# LM709_schematic.net
KiCad netlist of a schematic drawn in Altium Designer
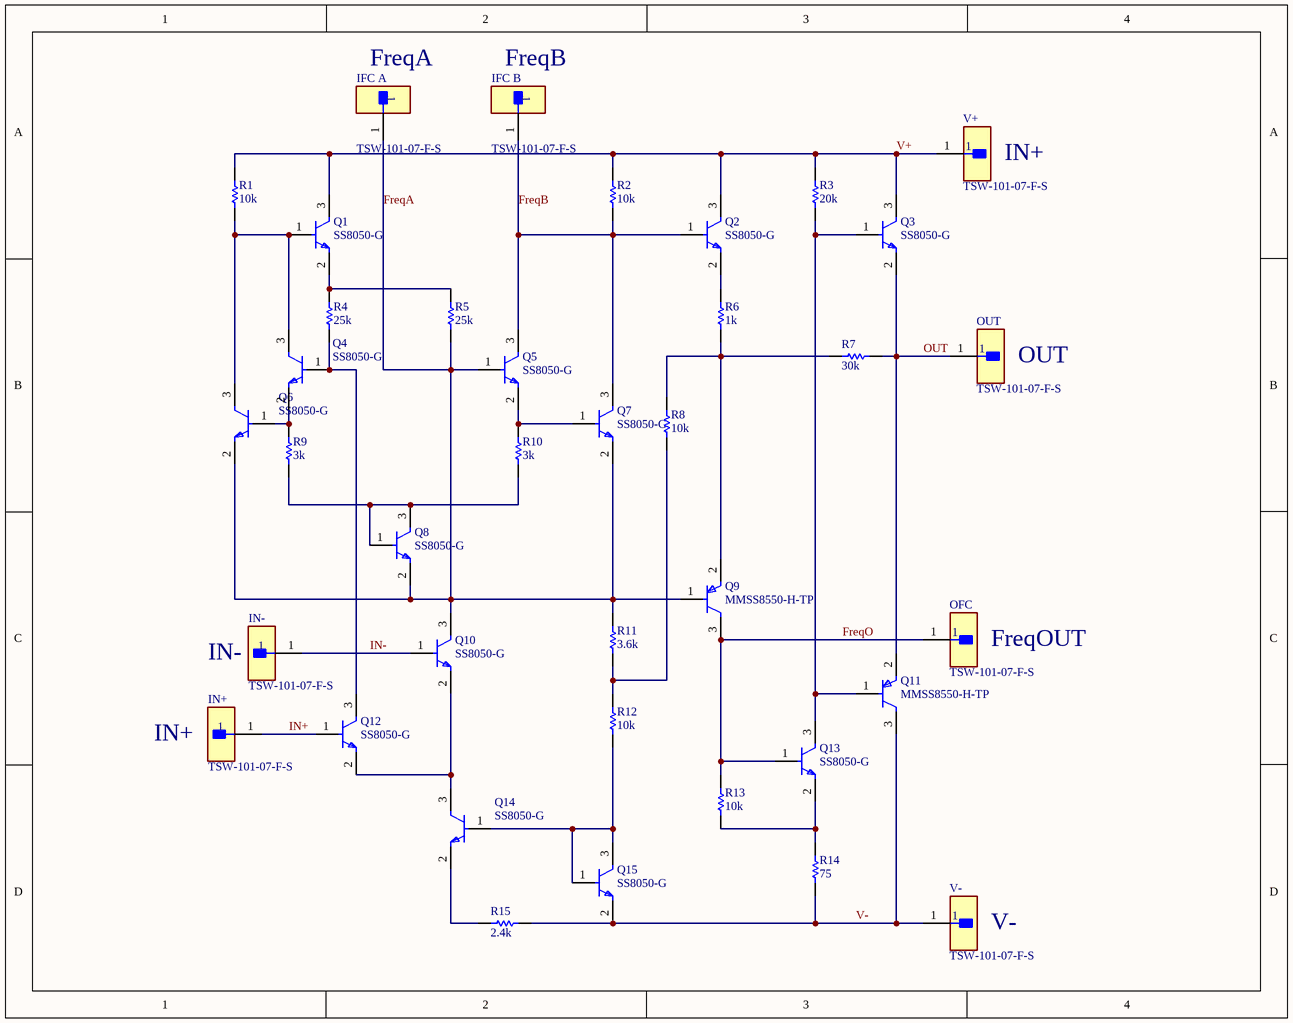
[diagram p0: LM709_schematic.SchDoc]

(export (version "E")
  (design (tool "Eeschema 10.0.6"))
  (components
    (comp (ref "IFC A")
      (value "TSW-101-07-F-S")
      (footprint "FP-TSW-101-07-F-S-MFG")
      (description "CONN HEADER VERT 1POS")
      (libsource (lib "") (part "dd45045ce8184df9e99e12baf3f412c_1"))
    )
    (comp (ref "IFC B")
      (value "TSW-101-07-F-S")
      (footprint "FP-TSW-101-07-F-S-MFG")
      (description "CONN HEADER VERT 1POS")
      (libsource (lib "") (part "dd45045ce8184df9e99e12baf3f412c_1"))
    )
    (comp (ref "IN+")
      (value "TSW-101-07-F-S")
      (footprint "FP-TSW-101-07-F-S-MFG")
      (description "CONN HEADER VERT 1POS")
      (libsource (lib "Altium Content Vault") (part "dd45045ce8184df9e99e12baf3f412c"))
    )
    (comp (ref "IN-")
      (value "TSW-101-07-F-S")
      (footprint "FP-TSW-101-07-F-S-MFG")
      (description "CONN HEADER VERT 1POS")
      (libsource (lib "Altium Content Vault") (part "dd45045ce8184df9e99e12baf3f412c"))
    )
    (comp (ref "OFC")
      (value "TSW-101-07-F-S")
      (footprint "FP-TSW-101-07-F-S-MFG")
      (description "CONN HEADER VERT 1POS")
      (libsource (lib "") (part "dd45045ce8184df9e99e12baf3f412c_1"))
    )
    (comp (ref "OUT")
      (value "TSW-101-07-F-S")
      (footprint "FP-TSW-101-07-F-S-MFG")
      (description "CONN HEADER VERT 1POS")
      (libsource (lib "") (part "dd45045ce8184df9e99e12baf3f412c_1"))
    )
    (comp (ref "Q1")
      (value "SS8050-G")
      (footprint "FP-SS8050-G-MFG")
      (description "NPN TRANSISTOR 1.5A 40V SOT-23 R")
      (libsource (lib "Altium Content Vault") (part "2a1388f82443b098dcd57d24ac7632d"))
    )
    (comp (ref "Q2")
      (value "SS8050-G")
      (footprint "FP-SS8050-G-MFG")
      (description "NPN TRANSISTOR 1.5A 40V SOT-23 R")
      (libsource (lib "Altium Content Vault") (part "2a1388f82443b098dcd57d24ac7632d"))
    )
    (comp (ref "Q3")
      (value "SS8050-G")
      (footprint "FP-SS8050-G-MFG")
      (description "NPN TRANSISTOR 1.5A 40V SOT-23 R")
      (libsource (lib "Altium Content Vault") (part "2a1388f82443b098dcd57d24ac7632d"))
    )
    (comp (ref "Q4")
      (value "SS8050-G")
      (footprint "FP-SS8050-G-MFG")
      (description "NPN TRANSISTOR 1.5A 40V SOT-23 R")
      (libsource (lib "Altium Content Vault") (part "2a1388f82443b098dcd57d24ac7632d"))
    )
    (comp (ref "Q5")
      (value "SS8050-G")
      (footprint "FP-SS8050-G-MFG")
      (description "NPN TRANSISTOR 1.5A 40V SOT-23 R")
      (libsource (lib "Altium Content Vault") (part "2a1388f82443b098dcd57d24ac7632d"))
    )
    (comp (ref "Q6")
      (value "SS8050-G")
      (footprint "FP-SS8050-G-MFG")
      (description "NPN TRANSISTOR 1.5A 40V SOT-23 R")
      (libsource (lib "Altium Content Vault") (part "2a1388f82443b098dcd57d24ac7632d"))
    )
    (comp (ref "Q7")
      (value "SS8050-G")
      (footprint "FP-SS8050-G-MFG")
      (description "NPN TRANSISTOR 1.5A 40V SOT-23 R")
      (libsource (lib "Altium Content Vault") (part "2a1388f82443b098dcd57d24ac7632d"))
    )
    (comp (ref "Q8")
      (value "SS8050-G")
      (footprint "FP-SS8050-G-MFG")
      (description "NPN TRANSISTOR 1.5A 40V SOT-23 R")
      (libsource (lib "Altium Content Vault") (part "2a1388f82443b098dcd57d24ac7632d"))
    )
    (comp (ref "Q9")
      (value "MMSS8550-H-TP")
      (footprint "FP-SOT-23-IPC_B")
      (description "TRANS PNP 25V 1.5A SOT23")
      (libsource (lib "Altium Content Vault") (part "0e8486ed3b47d9c69b8404ba87cf0f7"))
    )
    (comp (ref "Q10")
      (value "SS8050-G")
      (footprint "FP-SS8050-G-MFG")
      (description "NPN TRANSISTOR 1.5A 40V SOT-23 R")
      (libsource (lib "Altium Content Vault") (part "2a1388f82443b098dcd57d24ac7632d"))
    )
    (comp (ref "Q11")
      (value "MMSS8550-H-TP")
      (footprint "FP-SOT-23-IPC_B")
      (description "TRANS PNP 25V 1.5A SOT23")
      (libsource (lib "Altium Content Vault") (part "0e8486ed3b47d9c69b8404ba87cf0f7"))
    )
    (comp (ref "Q12")
      (value "SS8050-G")
      (footprint "FP-SS8050-G-MFG")
      (description "NPN TRANSISTOR 1.5A 40V SOT-23 R")
      (libsource (lib "Altium Content Vault") (part "2a1388f82443b098dcd57d24ac7632d"))
    )
    (comp (ref "Q13")
      (value "SS8050-G")
      (footprint "FP-SS8050-G-MFG")
      (description "NPN TRANSISTOR 1.5A 40V SOT-23 R")
      (libsource (lib "Altium Content Vault") (part "2a1388f82443b098dcd57d24ac7632d"))
    )
    (comp (ref "Q14")
      (value "SS8050-G")
      (footprint "FP-SS8050-G-MFG")
      (description "NPN TRANSISTOR 1.5A 40V SOT-23 R")
      (libsource (lib "Altium Content Vault") (part "2a1388f82443b098dcd57d24ac7632d"))
    )
    (comp (ref "Q15")
      (value "SS8050-G")
      (footprint "FP-SS8050-G-MFG")
      (description "NPN TRANSISTOR 1.5A 40V SOT-23 R")
      (libsource (lib "Altium Content Vault") (part "2a1388f82443b098dcd57d24ac7632d"))
    )
    (comp (ref "R1")
      (value "10k")
      (footprint "RESC2013X60X35ML10T20")
      (description "Chip Resistor, 1 KOhm, +/- 1%, 125 mW, -55 to 155 degC, 0805 (2012 Metric), RoHS, Tape and Reel")
      (fields (field (name "TOLERANCE") "1%") (field (name "MANUFACTURER") "Yageo"))
      (libsource (lib "Altium Content Vault") (part "RES-2"))
    )
    (comp (ref "R2")
      (value "10k")
      (footprint "RESC2013X60X35ML10T20")
      (description "Chip Resistor, 1 KOhm, +/- 1%, 125 mW, -55 to 155 degC, 0805 (2012 Metric), RoHS, Tape and Reel")
      (fields (field (name "TOLERANCE") "1%") (field (name "MANUFACTURER") "Yageo"))
      (libsource (lib "Altium Content Vault") (part "RES-2"))
    )
    (comp (ref "R3")
      (value "20k")
      (footprint "RESC2013X60X35ML10T20")
      (description "Chip Resistor, 1 KOhm, +/- 1%, 125 mW, -55 to 155 degC, 0805 (2012 Metric), RoHS, Tape and Reel")
      (fields (field (name "TOLERANCE") "1%") (field (name "MANUFACTURER") "Yageo"))
      (libsource (lib "Altium Content Vault") (part "RES-2"))
    )
    (comp (ref "R4")
      (value "25k")
      (footprint "RESC2013X60X35ML10T20")
      (description "Chip Resistor, 1 KOhm, +/- 1%, 125 mW, -55 to 155 degC, 0805 (2012 Metric), RoHS, Tape and Reel")
      (fields (field (name "TOLERANCE") "1%") (field (name "MANUFACTURER") "Yageo"))
      (libsource (lib "Altium Content Vault") (part "RES-2"))
    )
    (comp (ref "R5")
      (value "25k")
      (footprint "RESC2013X60X35ML10T20")
      (description "Chip Resistor, 1 KOhm, +/- 1%, 125 mW, -55 to 155 degC, 0805 (2012 Metric), RoHS, Tape and Reel")
      (fields (field (name "TOLERANCE") "1%") (field (name "MANUFACTURER") "Yageo"))
      (libsource (lib "Altium Content Vault") (part "RES-2"))
    )
    (comp (ref "R6")
      (value "1k")
      (footprint "RESC2013X60X35ML10T20")
      (description "Chip Resistor, 1 KOhm, +/- 1%, 125 mW, -55 to 155 degC, 0805 (2012 Metric), RoHS, Tape and Reel")
      (fields (field (name "TOLERANCE") "1%") (field (name "MANUFACTURER") "Yageo"))
      (libsource (lib "Altium Content Vault") (part "RES-2"))
    )
    (comp (ref "R7")
      (value "30k")
      (footprint "RESC2013X60X35ML10T20")
      (description "Chip Resistor, 1 KOhm, +/- 1%, 125 mW, -55 to 155 degC, 0805 (2012 Metric), RoHS, Tape and Reel")
      (fields (field (name "TOLERANCE") "1%") (field (name "MANUFACTURER") "Yageo"))
      (libsource (lib "Altium Content Vault") (part "RES-2"))
    )
    (comp (ref "R8")
      (value "10k")
      (footprint "RESC2013X60X35ML10T20")
      (description "Chip Resistor, 1 KOhm, +/- 1%, 125 mW, -55 to 155 degC, 0805 (2012 Metric), RoHS, Tape and Reel")
      (fields (field (name "TOLERANCE") "1%") (field (name "MANUFACTURER") "Yageo"))
      (libsource (lib "Altium Content Vault") (part "RES-2"))
    )
    (comp (ref "R9")
      (value "3k")
      (footprint "RESC2013X60X35ML10T20")
      (description "Chip Resistor, 1 KOhm, +/- 1%, 125 mW, -55 to 155 degC, 0805 (2012 Metric), RoHS, Tape and Reel")
      (fields (field (name "TOLERANCE") "1%") (field (name "MANUFACTURER") "Yageo"))
      (libsource (lib "Altium Content Vault") (part "RES-2"))
    )
    (comp (ref "R10")
      (value "3k")
      (footprint "RESC2013X60X35ML10T20")
      (description "Chip Resistor, 1 KOhm, +/- 1%, 125 mW, -55 to 155 degC, 0805 (2012 Metric), RoHS, Tape and Reel")
      (fields (field (name "TOLERANCE") "1%") (field (name "MANUFACTURER") "Yageo"))
      (libsource (lib "Altium Content Vault") (part "RES-2"))
    )
    (comp (ref "R11")
      (value "3.6k")
      (footprint "RESC2013X60X35ML10T20")
      (description "Chip Resistor, 1 KOhm, +/- 1%, 125 mW, -55 to 155 degC, 0805 (2012 Metric), RoHS, Tape and Reel")
      (fields (field (name "TOLERANCE") "1%") (field (name "MANUFACTURER") "Yageo"))
      (libsource (lib "Altium Content Vault") (part "RES-2"))
    )
    (comp (ref "R12")
      (value "10k")
      (footprint "RESC2013X60X35ML10T20")
      (description "Chip Resistor, 1 KOhm, +/- 1%, 125 mW, -55 to 155 degC, 0805 (2012 Metric), RoHS, Tape and Reel")
      (fields (field (name "TOLERANCE") "1%") (field (name "MANUFACTURER") "Yageo"))
      (libsource (lib "Altium Content Vault") (part "RES-2"))
    )
    (comp (ref "R13")
      (value "10k")
      (footprint "RESC2013X60X35ML10T20")
      (description "Chip Resistor, 1 KOhm, +/- 1%, 125 mW, -55 to 155 degC, 0805 (2012 Metric), RoHS, Tape and Reel")
      (fields (field (name "TOLERANCE") "1%") (field (name "MANUFACTURER") "Yageo"))
      (libsource (lib "Altium Content Vault") (part "RES-2"))
    )
    (comp (ref "R14")
      (value "75")
      (footprint "RESC2013X60X35ML10T20")
      (description "Chip Resistor, 1 KOhm, +/- 1%, 125 mW, -55 to 155 degC, 0805 (2012 Metric), RoHS, Tape and Reel")
      (fields (field (name "TOLERANCE") "1%") (field (name "MANUFACTURER") "Yageo"))
      (libsource (lib "Altium Content Vault") (part "RES-2"))
    )
    (comp (ref "R15")
      (value "2.4k")
      (footprint "RESC2013X60X35ML10T20")
      (description "Chip Resistor, 1 KOhm, +/- 1%, 125 mW, -55 to 155 degC, 0805 (2012 Metric), RoHS, Tape and Reel")
      (fields (field (name "TOLERANCE") "1%") (field (name "MANUFACTURER") "Yageo"))
      (libsource (lib "Altium Content Vault") (part "RES-2"))
    )
    (comp (ref "V+")
      (value "TSW-101-07-F-S")
      (footprint "FP-TSW-101-07-F-S-MFG")
      (description "CONN HEADER VERT 1POS")
      (libsource (lib "") (part "dd45045ce8184df9e99e12baf3f412c_1"))
    )
    (comp (ref "V-")
      (value "TSW-101-07-F-S")
      (footprint "FP-TSW-101-07-F-S-MFG")
      (description "CONN HEADER VERT 1POS")
      (libsource (lib "") (part "dd45045ce8184df9e99e12baf3f412c_1"))
    )
  )
  (nets
    (net (code "1") (name "/FreqA") (class "Default")
      (node (ref "IFC A") (pin "1") (pinfunction "1_1") (pintype "passive"))
      (node (ref "Q10") (pin "3") (pinfunction "C_3") (pintype "passive"))
      (node (ref "Q5") (pin "1") (pinfunction "B_1") (pintype "passive"))
      (node (ref "Q6") (pin "2") (pinfunction "E_2") (pintype "passive"))
      (node (ref "Q7") (pin "2") (pinfunction "E_2") (pintype "passive"))
      (node (ref "Q8") (pin "2") (pinfunction "E_2") (pintype "passive"))
      (node (ref "Q9") (pin "1") (pinfunction "B_1") (pintype "passive"))
      (node (ref "R11") (pin "2") (pinfunction "2_2") (pintype "passive"))
      (node (ref "R5") (pin "1") (pinfunction "1_1") (pintype "passive"))
    )
    (net (code "2") (name "/FreqB") (class "Default")
      (node (ref "IFC B") (pin "1") (pinfunction "1_1") (pintype "passive"))
      (node (ref "Q2") (pin "1") (pinfunction "B_1") (pintype "passive"))
      (node (ref "Q5") (pin "3") (pinfunction "C_3") (pintype "passive"))
      (node (ref "Q7") (pin "3") (pinfunction "C_3") (pintype "passive"))
      (node (ref "R2") (pin "1") (pinfunction "1_1") (pintype "passive"))
    )
    (net (code "3") (name "/FreqO") (class "Default")
      (node (ref "OFC") (pin "1") (pinfunction "1_1") (pintype "passive"))
      (node (ref "Q13") (pin "1") (pinfunction "B_1") (pintype "passive"))
      (node (ref "Q9") (pin "3") (pinfunction "C_3") (pintype "passive"))
      (node (ref "R13") (pin "2") (pinfunction "2_2") (pintype "passive"))
    )
    (net (code "4") (name "/IN+") (class "Default")
      (node (ref "IN+") (pin "1") (pinfunction "1_1") (pintype "passive"))
      (node (ref "Q12") (pin "1") (pinfunction "B_1") (pintype "passive"))
    )
    (net (code "5") (name "/IN-") (class "Default")
      (node (ref "IN-") (pin "1") (pinfunction "1_1") (pintype "passive"))
      (node (ref "Q10") (pin "1") (pinfunction "B_1") (pintype "passive"))
    )
    (net (code "6") (name "/OUT") (class "Default")
      (node (ref "OUT") (pin "1") (pinfunction "1_1") (pintype "passive"))
      (node (ref "Q11") (pin "2") (pinfunction "E_2") (pintype "passive"))
      (node (ref "Q3") (pin "2") (pinfunction "E_2") (pintype "passive"))
      (node (ref "R7") (pin "1") (pinfunction "1_1") (pintype "passive"))
    )
    (net (code "7") (name "/V+") (class "Default")
      (node (ref "Q1") (pin "3") (pinfunction "C_3") (pintype "passive"))
      (node (ref "Q2") (pin "3") (pinfunction "C_3") (pintype "passive"))
      (node (ref "Q3") (pin "3") (pinfunction "C_3") (pintype "passive"))
      (node (ref "R1") (pin "2") (pinfunction "2_2") (pintype "passive"))
      (node (ref "R2") (pin "2") (pinfunction "2_2") (pintype "passive"))
      (node (ref "R3") (pin "2") (pinfunction "2_2") (pintype "passive"))
      (node (ref "V+") (pin "1") (pinfunction "1_1") (pintype "passive"))
    )
    (net (code "8") (name "/V-") (class "Default")
      (node (ref "Q11") (pin "3") (pinfunction "C_3") (pintype "passive"))
      (node (ref "Q15") (pin "2") (pinfunction "E_2") (pintype "passive"))
      (node (ref "R14") (pin "1") (pinfunction "1_1") (pintype "passive"))
      (node (ref "R15") (pin "2") (pinfunction "2_2") (pintype "passive"))
      (node (ref "V-") (pin "1") (pinfunction "1_1") (pintype "passive"))
    )
    (net (code "9") (name "Net-(Q1-B)") (class "Default")
      (node (ref "Q1") (pin "1") (pinfunction "B_1") (pintype "passive"))
      (node (ref "Q4") (pin "3") (pinfunction "C_3") (pintype "passive"))
      (node (ref "Q6") (pin "3") (pinfunction "C_3") (pintype "passive"))
      (node (ref "R1") (pin "1") (pinfunction "1_1") (pintype "passive"))
    )
    (net (code "10") (name "Net-(Q1-E)") (class "Default")
      (node (ref "Q1") (pin "2") (pinfunction "E_2") (pintype "passive"))
      (node (ref "R4") (pin "2") (pinfunction "2_2") (pintype "passive"))
      (node (ref "R5") (pin "2") (pinfunction "2_2") (pintype "passive"))
    )
    (net (code "11") (name "Net-(Q2-E)") (class "Default")
      (node (ref "Q2") (pin "2") (pinfunction "E_2") (pintype "passive"))
      (node (ref "R6") (pin "2") (pinfunction "2_2") (pintype "passive"))
    )
    (net (code "12") (name "Net-(Q4-E)") (class "Default")
      (node (ref "Q4") (pin "2") (pinfunction "E_2") (pintype "passive"))
      (node (ref "Q6") (pin "1") (pinfunction "B_1") (pintype "passive"))
      (node (ref "R9") (pin "2") (pinfunction "2_2") (pintype "passive"))
    )
    (net (code "13") (name "Net-(Q5-E)") (class "Default")
      (node (ref "Q5") (pin "2") (pinfunction "E_2") (pintype "passive"))
      (node (ref "Q7") (pin "1") (pinfunction "B_1") (pintype "passive"))
      (node (ref "R10") (pin "2") (pinfunction "2_2") (pintype "passive"))
    )
    (net (code "14") (name "Net-(Q8-B)") (class "Default")
      (node (ref "Q8") (pin "1") (pinfunction "B_1") (pintype "passive"))
      (node (ref "Q8") (pin "3") (pinfunction "C_3") (pintype "passive"))
      (node (ref "R10") (pin "1") (pinfunction "1_1") (pintype "passive"))
      (node (ref "R9") (pin "1") (pinfunction "1_1") (pintype "passive"))
    )
    (net (code "15") (name "Net-(Q9-E)") (class "Default")
      (node (ref "Q9") (pin "2") (pinfunction "E_2") (pintype "passive"))
      (node (ref "R6") (pin "1") (pinfunction "1_1") (pintype "passive"))
      (node (ref "R7") (pin "2") (pinfunction "2_2") (pintype "passive"))
      (node (ref "R8") (pin "2") (pinfunction "2_2") (pintype "passive"))
    )
    (net (code "16") (name "Net-(Q10-E)") (class "Default")
      (node (ref "Q10") (pin "2") (pinfunction "E_2") (pintype "passive"))
      (node (ref "Q12") (pin "2") (pinfunction "E_2") (pintype "passive"))
      (node (ref "Q14") (pin "3") (pinfunction "C_3") (pintype "passive"))
    )
    (net (code "17") (name "Net-(Q11-B)") (class "Default")
      (node (ref "Q11") (pin "1") (pinfunction "B_1") (pintype "passive"))
      (node (ref "Q13") (pin "3") (pinfunction "C_3") (pintype "passive"))
      (node (ref "Q3") (pin "1") (pinfunction "B_1") (pintype "passive"))
      (node (ref "R3") (pin "1") (pinfunction "1_1") (pintype "passive"))
    )
    (net (code "18") (name "Net-(Q12-C)") (class "Default")
      (node (ref "Q12") (pin "3") (pinfunction "C_3") (pintype "passive"))
      (node (ref "Q4") (pin "1") (pinfunction "B_1") (pintype "passive"))
      (node (ref "R4") (pin "1") (pinfunction "1_1") (pintype "passive"))
    )
    (net (code "19") (name "Net-(Q13-E)") (class "Default")
      (node (ref "Q13") (pin "2") (pinfunction "E_2") (pintype "passive"))
      (node (ref "R13") (pin "1") (pinfunction "1_1") (pintype "passive"))
      (node (ref "R14") (pin "2") (pinfunction "2_2") (pintype "passive"))
    )
    (net (code "20") (name "Net-(Q14-B)") (class "Default")
      (node (ref "Q14") (pin "1") (pinfunction "B_1") (pintype "passive"))
      (node (ref "Q15") (pin "1") (pinfunction "B_1") (pintype "passive"))
      (node (ref "Q15") (pin "3") (pinfunction "C_3") (pintype "passive"))
      (node (ref "R12") (pin "1") (pinfunction "1_1") (pintype "passive"))
    )
    (net (code "21") (name "Net-(Q14-E)") (class "Default")
      (node (ref "Q14") (pin "2") (pinfunction "E_2") (pintype "passive"))
      (node (ref "R15") (pin "1") (pinfunction "1_1") (pintype "passive"))
    )
    (net (code "22") (name "Net-(R11-Pad1)") (class "Default")
      (node (ref "R11") (pin "1") (pinfunction "1_1") (pintype "passive"))
      (node (ref "R12") (pin "2") (pinfunction "2_2") (pintype "passive"))
      (node (ref "R8") (pin "1") (pinfunction "1_1") (pintype "passive"))
    )
  )
)
